# Sheet1.net
KiCad netlist of a schematic drawn in Altium Designer
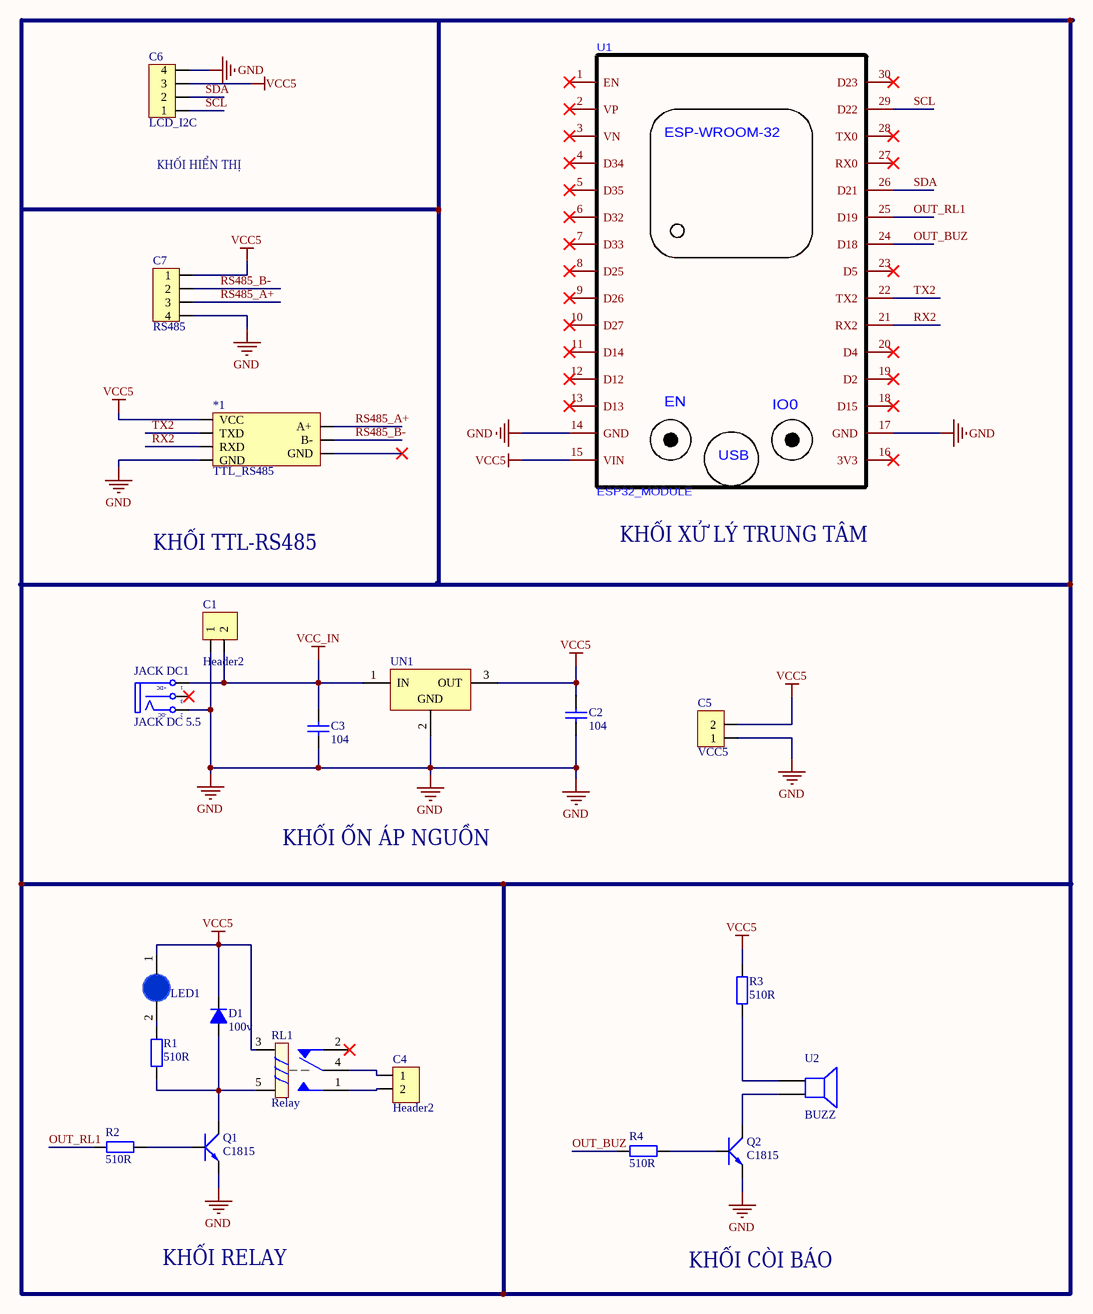
[diagram p0: Sheet1.SchDoc]

(export (version "E")
  (design (tool "Eeschema 10.0.6"))
  (components
    (comp (ref "*1")
      (value "TTL_RS485")
      (footprint "RS-485 Module")
      (libsource (lib "myLib_v1") (part "TTL_RS485"))
    )
    (comp (ref "C1")
      (value "Header2")
      (footprint "Header2")
      (description "Header IDC, 2 x 1 Pin Vertical 2.54mm Pitch (Non-Boxed, Male)")
      (fields
        (field (name "MANUFACTURER") "Würth Elektronik eiSos GmbH")
        (field (name "PARTNO") "613002143121")
        (field (name "CREATED BY") "Karrer Zheng")
      )
      (libsource (lib "") (part "Header2_1"))
    )
    (comp (ref "C2")
      (value "104")
      (footprint "tu gom")
      (description "Cắm")
      (libsource (lib "Altium_Lib_by_KhueNguyenCreator") (part "Tu gom 104 50V"))
    )
    (comp (ref "C3")
      (value "104")
      (footprint "tu gom")
      (description "Cắm")
      (libsource (lib "Altium_Lib_by_KhueNguyenCreator") (part "Tu gom 104 50V"))
    )
    (comp (ref "C4")
      (value "Header2")
      (footprint "Header2")
      (description "Header IDC, 2 x 1 Pin Vertical 2.54mm Pitch (Non-Boxed, Male)")
      (fields
        (field (name "MANUFACTURER") "Würth Elektronik eiSos GmbH")
        (field (name "PARTNO") "613002143121")
        (field (name "CREATED BY") "Karrer Zheng")
      )
      (libsource (lib "myLib_v1") (part "Header2"))
    )
    (comp (ref "C5")
      (value "VCC5")
      (footprint "Header2")
      (description "Header IDC, 2 x 1 Pin Vertical 2.54mm Pitch (Non-Boxed, Male)")
      (fields
        (field (name "MANUFACTURER") "Würth Elektronik eiSos GmbH")
        (field (name "PARTNO") "613002143121")
        (field (name "CREATED BY") "Karrer Zheng")
      )
      (libsource (lib "") (part "Header2_2"))
    )
    (comp (ref "C6")
      (value "LCD_I2C")
      (footprint "Header4")
      (description "Header IDC, 4 x 1 Pin Vertical 2.54mm Pitch (Non-Boxed, Male)")
      (fields
        (field (name "MANUFACTURER") "Würth Elektronik eiSos GmbH")
        (field (name "PARTNO") "613002143121")
        (field (name "CREATED BY") "Karrer Zheng")
      )
      (libsource (lib "myLib_v1") (part "Header4"))
    )
    (comp (ref "C7")
      (value "RS485")
      (footprint "Header4")
      (description "Header IDC, 4 x 1 Pin Vertical 2.54mm Pitch (Non-Boxed, Male)")
      (fields
        (field (name "MANUFACTURER") "Würth Elektronik eiSos GmbH")
        (field (name "PARTNO") "613002143121")
        (field (name "CREATED BY") "Karrer Zheng")
      )
      (libsource (lib "") (part "Header4_1"))
    )
    (comp (ref "D1")
      (value "100v")
      (footprint "DIODE 0.5A")
      (description "Cắm")
      (libsource (lib "Altium_Lib_by_KhueNguyenCreator") (part "Diode 1N4148"))
    )
    (comp (ref "JACK DC1")
      (value "JACK DC 5.5")
      (footprint "JACK DC 5.5")
      (libsource (lib "Altium_Lib_by_KhueNguyenCreator") (part "JACK DC 5.5"))
    )
    (comp (ref "LED1")
      (value "LED 3mm")
      (footprint "LED-3MM-BLUE")
      (description "Cắm")
      (libsource (lib "myLib_v1") (part "LED 3mm Xanh Duong"))
    )
    (comp (ref "Q1")
      (value "C1815")
      (footprint "C1815_cam")
      (description "NPN 600mW, ECB")
      (libsource (lib "myLib_v1") (part "C1815"))
    )
    (comp (ref "Q2")
      (value "C1815")
      (footprint "C1815_cam")
      (description "NPN 600mW, ECB")
      (libsource (lib "myLib_v1") (part "C1815"))
    )
    (comp (ref "R1")
      (value "510R")
      (footprint "R1/4W")
      (description "Resistor 1/4W")
      (libsource (lib "myLib_v1") (part "R1/4W"))
    )
    (comp (ref "R2")
      (value "510R")
      (footprint "R1/4W")
      (description "Resistor 1/4W")
      (libsource (lib "myLib_v1") (part "R1/4W"))
    )
    (comp (ref "R3")
      (value "510R")
      (footprint "R1/4W")
      (description "Resistor 1/4W")
      (libsource (lib "myLib_v1") (part "R1/4W"))
    )
    (comp (ref "R4")
      (value "510R")
      (footprint "R1/4W")
      (description "Resistor 1/4W")
      (libsource (lib "myLib_v1") (part "R1/4W"))
    )
    (comp (ref "RL1")
      (value "Relay")
      (footprint "RELAY_SRA_05VDC_SL_C")
      (description "Relay 5 Chan")
      (libsource (lib "myLib_v1") (part "RL_SRA-05VDC-SL-C"))
    )
    (comp (ref "U1")
      (value "ESP32_MODULE")
      (footprint "ESP32-WIFIMODULE-FOOTPRINT")
      (libsource (lib "myLib_v1") (part "ESP32_MODULE copy"))
    )
    (comp (ref "U2")
      (value "BUZZ")
      (footprint "BUZZER_D9_TH")
      (description "Loudspeaker")
      (libsource (lib "BYTECH_HW_LIB_2019 (1)") (part "Speaker"))
    )
    (comp (ref "UN1")
      (value "L78M05CP")
      (footprint "QTO-220H2")
      (description "Positive Voltage Regulator")
      (fields (field (name "PUBLISHER") "Altium Limited"))
      (libsource (lib "syhaunguyen") (part "L78M05CP"))
    )
  )
  (nets
    (net (code "1") (name "/OUT_BUZ") (class "Default")
      (node (ref "R4") (pin "1") (pinfunction "1_1") (pintype "passive"))
      (node (ref "U1") (pin "24") (pinfunction "D18_24") (pintype "passive"))
    )
    (net (code "2") (name "/OUT_RL1") (class "Default")
      (node (ref "R2") (pin "1") (pinfunction "1_1") (pintype "passive"))
      (node (ref "U1") (pin "25") (pinfunction "D19_25") (pintype "passive"))
    )
    (net (code "3") (name "/RS485_A+") (class "Default")
      (node (ref "*1") (pin "7") (pinfunction "A+_7") (pintype "passive"))
      (node (ref "C7") (pin "3") (pinfunction "3_3") (pintype "passive"))
    )
    (net (code "4") (name "/RS485_B-") (class "Default")
      (node (ref "*1") (pin "6") (pinfunction "B-_6") (pintype "passive"))
      (node (ref "C7") (pin "2") (pinfunction "2_2") (pintype "passive"))
    )
    (net (code "5") (name "/RX2") (class "Default")
      (node (ref "*1") (pin "3") (pinfunction "RXD_3") (pintype "passive"))
      (node (ref "U1") (pin "21") (pinfunction "RX2_21") (pintype "passive"))
    )
    (net (code "6") (name "/SCL") (class "Default")
      (node (ref "C6") (pin "1") (pinfunction "1_1") (pintype "passive"))
      (node (ref "U1") (pin "29") (pinfunction "D22_29") (pintype "passive"))
    )
    (net (code "7") (name "/SDA") (class "Default")
      (node (ref "C6") (pin "2") (pinfunction "2_2") (pintype "passive"))
      (node (ref "U1") (pin "26") (pinfunction "D21_26") (pintype "passive"))
    )
    (net (code "8") (name "/TX2") (class "Default")
      (node (ref "*1") (pin "2") (pinfunction "TXD_2") (pintype "passive"))
      (node (ref "U1") (pin "22") (pinfunction "TX2_22") (pintype "passive"))
    )
    (net (code "9") (name "GND") (class "Default")
      (node (ref "*1") (pin "4") (pinfunction "GND_4") (pintype "passive"))
      (node (ref "C1") (pin "1") (pinfunction "1_1") (pintype "passive"))
      (node (ref "C2") (pin "2") (pinfunction "2_2") (pintype "passive"))
      (node (ref "C3") (pin "2") (pinfunction "2_2") (pintype "passive"))
      (node (ref "C5") (pin "1") (pinfunction "1_1") (pintype "passive"))
      (node (ref "C6") (pin "4") (pinfunction "4_4") (pintype "passive"))
      (node (ref "C7") (pin "4") (pinfunction "4_4") (pintype "passive"))
      (node (ref "JACK DC1") (pin "2") (pinfunction "TN_2") (pintype "passive"))
      (node (ref "Q1") (pin "1") (pinfunction "E_1") (pintype "passive"))
      (node (ref "Q2") (pin "1") (pinfunction "E_1") (pintype "passive"))
      (node (ref "U1") (pin "14") (pinfunction "GND_14") (pintype "passive"))
      (node (ref "U1") (pin "17") (pinfunction "GND_17") (pintype "passive"))
      (node (ref "UN1") (pin "2") (pinfunction "GND_2") (pintype "power_in"))
    )
    (net (code "10") (name "Net-(C4-Pad1)") (class "Default")
      (node (ref "C4") (pin "1") (pinfunction "1_1") (pintype "passive"))
      (node (ref "RL1") (pin "4") (pinfunction "4_4") (pintype "passive"))
    )
    (net (code "11") (name "Net-(C4-Pad2)") (class "Default")
      (node (ref "C4") (pin "2") (pinfunction "2_2") (pintype "passive"))
      (node (ref "RL1") (pin "1") (pinfunction "1_1") (pintype "passive"))
    )
    (net (code "12") (name "Net-(D1-A)") (class "Default")
      (node (ref "D1") (pin "1") (pinfunction "A_1") (pintype "passive"))
      (node (ref "Q1") (pin "2") (pinfunction "C_2") (pintype "passive"))
      (node (ref "R1") (pin "2") (pinfunction "2_2") (pintype "passive"))
      (node (ref "RL1") (pin "5") (pinfunction "5_5") (pintype "passive"))
    )
    (net (code "13") (name "Net-(LED1-K)") (class "Default")
      (node (ref "LED1") (pin "2") (pinfunction "K_2") (pintype "passive"))
      (node (ref "R1") (pin "1") (pinfunction "1_1") (pintype "passive"))
    )
    (net (code "14") (name "Net-(Q1-B)") (class "Default")
      (node (ref "Q1") (pin "3") (pinfunction "B_3") (pintype "passive"))
      (node (ref "R2") (pin "2") (pinfunction "2_2") (pintype "passive"))
    )
    (net (code "15") (name "Net-(Q2-B)") (class "Default")
      (node (ref "Q2") (pin "3") (pinfunction "B_3") (pintype "passive"))
      (node (ref "R4") (pin "2") (pinfunction "2_2") (pintype "passive"))
    )
    (net (code "16") (name "Net-(Q2-C)") (class "Default")
      (node (ref "Q2") (pin "2") (pinfunction "C_2") (pintype "passive"))
      (node (ref "U2") (pin "2") (pinfunction "2_2") (pintype "passive"))
    )
    (net (code "17") (name "Net-(R3-Pad2)") (class "Default")
      (node (ref "R3") (pin "2") (pinfunction "2_2") (pintype "passive"))
      (node (ref "U2") (pin "1") (pinfunction "1_1") (pintype "passive"))
    )
    (net (code "18") (name "VCC5") (class "Default")
      (node (ref "*1") (pin "1") (pinfunction "VCC_1") (pintype "passive"))
      (node (ref "C2") (pin "1") (pinfunction "1_1") (pintype "passive"))
      (node (ref "C5") (pin "2") (pinfunction "2_2") (pintype "passive"))
      (node (ref "C6") (pin "3") (pinfunction "3_3") (pintype "passive"))
      (node (ref "C7") (pin "1") (pinfunction "1_1") (pintype "passive"))
      (node (ref "D1") (pin "2") (pinfunction "K_2") (pintype "passive"))
      (node (ref "LED1") (pin "1") (pinfunction "A_1") (pintype "passive"))
      (node (ref "R3") (pin "1") (pinfunction "1_1") (pintype "passive"))
      (node (ref "RL1") (pin "3") (pinfunction "3_3") (pintype "passive"))
      (node (ref "U1") (pin "15") (pinfunction "VIN_15") (pintype "passive"))
      (node (ref "UN1") (pin "3") (pinfunction "OUT_3") (pintype "power_in"))
    )
    (net (code "19") (name "VCC_IN") (class "Default")
      (node (ref "C1") (pin "2") (pinfunction "2_2") (pintype "passive"))
      (node (ref "C3") (pin "1") (pinfunction "1_1") (pintype "passive"))
      (node (ref "JACK DC1") (pin "1") (pinfunction "T_1") (pintype "passive"))
      (node (ref "UN1") (pin "1") (pinfunction "IN_1") (pintype "power_in"))
    )
    (net (code "20") (name "unconnected-(*1-GND-Pad5)") (class "Default")
      (node (ref "*1") (pin "5") (pinfunction "GND_5") (pintype "passive+no_connect"))
    )
    (net (code "21") (name "unconnected-(JACK DC1-S-Pad3)") (class "Default")
      (node (ref "JACK DC1") (pin "3") (pinfunction "S_3") (pintype "power_in+no_connect"))
    )
    (net (code "22") (name "unconnected-(RL1-Pad2)") (class "Default")
      (node (ref "RL1") (pin "2") (pinfunction "2_2") (pintype "passive+no_connect"))
    )
    (net (code "23") (name "unconnected-(U1-3V3-Pad16)") (class "Default")
      (node (ref "U1") (pin "16") (pinfunction "3V3_16") (pintype "passive+no_connect"))
    )
    (net (code "24") (name "unconnected-(U1-D2-Pad19)") (class "Default")
      (node (ref "U1") (pin "19") (pinfunction "D2_19") (pintype "passive+no_connect"))
    )
    (net (code "25") (name "unconnected-(U1-D4-Pad20)") (class "Default")
      (node (ref "U1") (pin "20") (pinfunction "D4_20") (pintype "passive+no_connect"))
    )
    (net (code "26") (name "unconnected-(U1-D5-Pad23)") (class "Default")
      (node (ref "U1") (pin "23") (pinfunction "D5_23") (pintype "passive+no_connect"))
    )
    (net (code "27") (name "unconnected-(U1-D12-Pad12)") (class "Default")
      (node (ref "U1") (pin "12") (pinfunction "D12_12") (pintype "passive+no_connect"))
    )
    (net (code "28") (name "unconnected-(U1-D13-Pad13)") (class "Default")
      (node (ref "U1") (pin "13") (pinfunction "D13_13") (pintype "passive+no_connect"))
    )
    (net (code "29") (name "unconnected-(U1-D14-Pad11)") (class "Default")
      (node (ref "U1") (pin "11") (pinfunction "D14_11") (pintype "passive+no_connect"))
    )
    (net (code "30") (name "unconnected-(U1-D15-Pad18)") (class "Default")
      (node (ref "U1") (pin "18") (pinfunction "D15_18") (pintype "passive+no_connect"))
    )
    (net (code "31") (name "unconnected-(U1-D23-Pad30)") (class "Default")
      (node (ref "U1") (pin "30") (pinfunction "D23_30") (pintype "passive+no_connect"))
    )
    (net (code "32") (name "unconnected-(U1-D25-Pad8)") (class "Default")
      (node (ref "U1") (pin "8") (pinfunction "D25_8") (pintype "passive+no_connect"))
    )
    (net (code "33") (name "unconnected-(U1-D26-Pad9)") (class "Default")
      (node (ref "U1") (pin "9") (pinfunction "D26_9") (pintype "passive+no_connect"))
    )
    (net (code "34") (name "unconnected-(U1-D27-Pad10)") (class "Default")
      (node (ref "U1") (pin "10") (pinfunction "D27_10") (pintype "passive+no_connect"))
    )
    (net (code "35") (name "unconnected-(U1-D32-Pad6)") (class "Default")
      (node (ref "U1") (pin "6") (pinfunction "D32_6") (pintype "passive+no_connect"))
    )
    (net (code "36") (name "unconnected-(U1-D33-Pad7)") (class "Default")
      (node (ref "U1") (pin "7") (pinfunction "D33_7") (pintype "passive+no_connect"))
    )
    (net (code "37") (name "unconnected-(U1-D34-Pad4)") (class "Default")
      (node (ref "U1") (pin "4") (pinfunction "D34_4") (pintype "passive+no_connect"))
    )
    (net (code "38") (name "unconnected-(U1-D35-Pad5)") (class "Default")
      (node (ref "U1") (pin "5") (pinfunction "D35_5") (pintype "passive+no_connect"))
    )
    (net (code "39") (name "unconnected-(U1-EN-Pad1)") (class "Default")
      (node (ref "U1") (pin "1") (pinfunction "EN_1") (pintype "passive+no_connect"))
    )
    (net (code "40") (name "unconnected-(U1-RX0-Pad27)") (class "Default")
      (node (ref "U1") (pin "27") (pinfunction "RX0_27") (pintype "passive+no_connect"))
    )
    (net (code "41") (name "unconnected-(U1-TX0-Pad28)") (class "Default")
      (node (ref "U1") (pin "28") (pinfunction "TX0_28") (pintype "passive+no_connect"))
    )
    (net (code "42") (name "unconnected-(U1-VN-Pad3)") (class "Default")
      (node (ref "U1") (pin "3") (pinfunction "VN_3") (pintype "passive+no_connect"))
    )
    (net (code "43") (name "unconnected-(U1-VP-Pad2)") (class "Default")
      (node (ref "U1") (pin "2") (pinfunction "VP_2") (pintype "passive+no_connect"))
    )
  )
)
